# Mainboard_RMII_Interface.net
KiCad netlist of a schematic drawn in Altium Designer
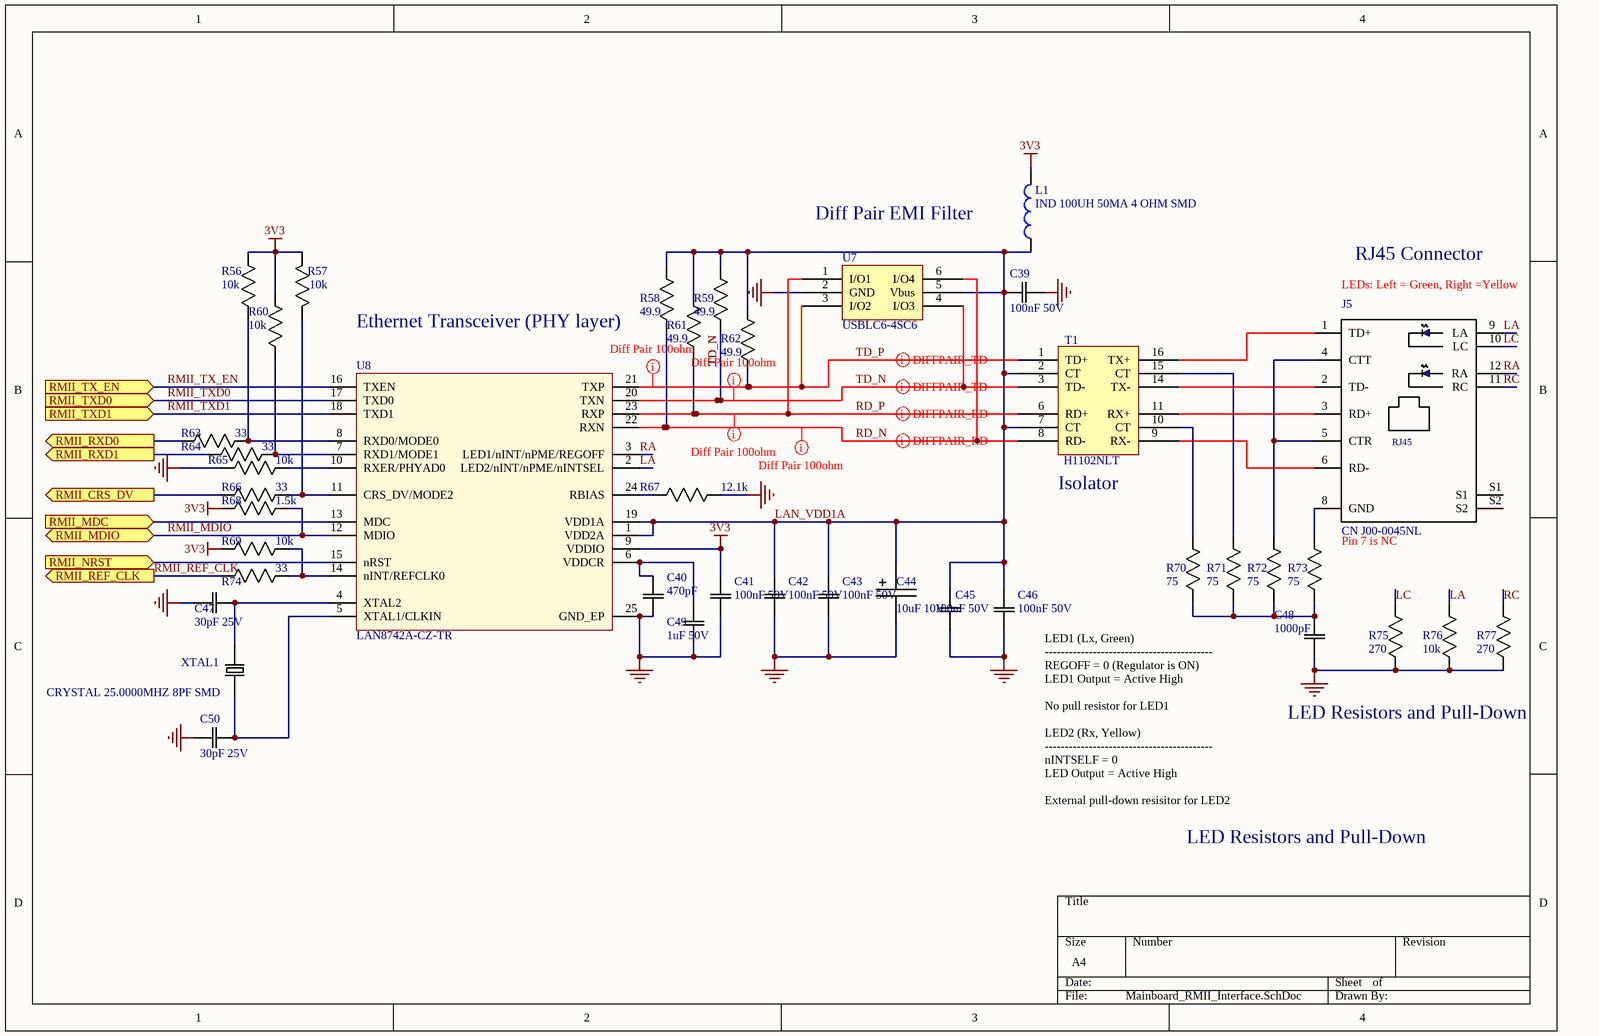
[diagram p0: Mainboard_RMII_Interface.SchDoc]

(export (version "E")
  (design (tool "Eeschema 10.0.6"))
  (components
    (comp (ref "C39")
      (value "100nF 50V")
      (footprint "0805")
      (description "CAP CER 0.1UF 50V X7R 0805")
      (fields (field (name "TOLERANCE") "10%"))
      (libsource (lib "") (part "CAP 100nF 50V_1"))
    )
    (comp (ref "C40")
      (value "470pF")
      (footprint "0805")
      (description "CAP CER 470PF 50V X7R 0603/0805")
      (fields (field (name "TOLERANCE") "10%"))
      (libsource (lib "AltiumLibraries") (part "CAP 470pF 50V"))
    )
    (comp (ref "C41")
      (value "100nF 50V")
      (footprint "0805")
      (description "CAP CER 0.1UF 50V X7R 0805")
      (fields (field (name "TOLERANCE") "10%"))
      (libsource (lib "AltiumLibraries") (part "CAP 100nF 50V"))
    )
    (comp (ref "C42")
      (value "100nF 50V")
      (footprint "0805")
      (description "CAP CER 0.1UF 50V X7R 0805")
      (fields (field (name "TOLERANCE") "10%"))
      (libsource (lib "AltiumLibraries") (part "CAP 100nF 50V"))
    )
    (comp (ref "C43")
      (value "100nF 50V")
      (footprint "0805")
      (description "CAP CER 0.1UF 50V X7R 0805")
      (fields (field (name "TOLERANCE") "10%"))
      (libsource (lib "AltiumLibraries") (part "CAP 100nF 50V"))
    )
    (comp (ref "C44")
      (value "10uF 10V")
      (footprint "1206 Polarized")
      (description "CAP TANT 10UF 10V 1206")
      (fields (field (name "TOLERANCE") "10%"))
      (libsource (lib "AltiumLibraries") (part "CAP TANT 10uF 10V"))
    )
    (comp (ref "C45")
      (value "100nF 50V")
      (footprint "0805")
      (description "CAP CER 0.1UF 50V X7R 0805")
      (fields (field (name "TOLERANCE") "10%"))
      (libsource (lib "AltiumLibraries") (part "CAP 100nF 50V"))
    )
    (comp (ref "C46")
      (value "100nF 50V")
      (footprint "0805")
      (description "CAP CER 0.1UF 50V X7R 0805")
      (fields (field (name "TOLERANCE") "10%"))
      (libsource (lib "AltiumLibraries") (part "CAP 100nF 50V"))
    )
    (comp (ref "C47")
      (value "30pF 25V")
      (footprint "0805")
      (description "CAP CER 30PF 25V NP0 0805")
      (fields (field (name "TOLERANCE") "20%"))
      (libsource (lib "AltiumLibraries") (part "CAP 30pF 25V"))
    )
    (comp (ref "C48")
      (value "1000pF")
      (footprint "0603")
      (description "CAP CER 1000PF 50V X7R 0603/0805")
      (fields (field (name "TOLERANCE") "10%"))
      (libsource (lib "AltiumLibraries") (part "CAP 1000pF 50V"))
    )
    (comp (ref "C49")
      (value "1uF 50V")
      (footprint "0805")
      (description "CAP CER 1UF 50V X7R 0805")
      (fields (field (name "TOLERANCE") "10%"))
      (libsource (lib "AltiumLibraries") (part "CAP 1uF 50V"))
    )
    (comp (ref "C50")
      (value "30pF 25V")
      (footprint "0805")
      (description "CAP CER 30PF 25V NP0 0805")
      (fields (field (name "TOLERANCE") "20%"))
      (libsource (lib "AltiumLibraries") (part "CAP 30pF 25V"))
    )
    (comp (ref "J5")
      (value "CN J00-0045NL")
      (footprint "RJ45 J00-0045NL")
      (description "CN MAGJACK 1PORT 100 BASE-TX")
      (fields (field (name "MF") "Pulse Electronics") (field (name "MP") "J00-0045NL"))
      (libsource (lib "AltiumLibraries") (part "CN MAGJACK"))
    )
    (comp (ref "L1")
      (value "IND 100UH 50MA 4 OHM SMD")
      (footprint "0805")
      (description "100µH Unshielded Wirewound Inductor 50mA 4Ohm 0805 (2012 Metric)")
      (fields (field (name "MF") "Taiyo Yuden") (field (name "MP") "LBR2012T101K"))
      (libsource (lib "AltiumLibraries") (part "IND 100UH 50MA 4 OHM SMD"))
    )
    (comp (ref "R56")
      (value "10k")
      (footprint "0805")
      (description "RES SMD 10K OHM 1% 1/8W 0805")
      (fields (field (name "TOLERANCE") "1%"))
      (libsource (lib "") (part "RES 10k 1/8W - 1%_1"))
    )
    (comp (ref "R57")
      (value "10k")
      (footprint "0805")
      (description "RES SMD 10K OHM 1% 1/8W 0805")
      (fields (field (name "TOLERANCE") "1%"))
      (libsource (lib "") (part "RES 10k 1/8W - 1%_1"))
    )
    (comp (ref "R58")
      (value "49.9")
      (footprint "0805")
      (description "RES SMD 49.9 OHM 1% 1/8W 0805")
      (fields (field (name "TOLERANCE") "1%"))
      (libsource (lib "AltiumLibraries") (part "RES 49.9 1/8W"))
    )
    (comp (ref "R59")
      (value "49.9")
      (footprint "0805")
      (description "RES SMD 49.9 OHM 1% 1/8W 0805")
      (fields (field (name "TOLERANCE") "1%"))
      (libsource (lib "AltiumLibraries") (part "RES 49.9 1/8W"))
    )
    (comp (ref "R60")
      (value "10k")
      (footprint "0805")
      (description "RES SMD 10K OHM 1% 1/8W 0805")
      (fields (field (name "TOLERANCE") "1%"))
      (libsource (lib "") (part "RES 10k 1/8W - 1%_1"))
    )
    (comp (ref "R61")
      (value "49.9")
      (footprint "0805")
      (description "RES SMD 49.9 OHM 1% 1/8W 0805")
      (fields (field (name "TOLERANCE") "1%"))
      (libsource (lib "AltiumLibraries") (part "RES 49.9 1/8W"))
    )
    (comp (ref "R62")
      (value "49.9")
      (footprint "0805")
      (description "RES SMD 49.9 OHM 1% 1/8W 0805")
      (fields (field (name "TOLERANCE") "1%"))
      (libsource (lib "AltiumLibraries") (part "RES 49.9 1/8W"))
    )
    (comp (ref "R63")
      (value "33")
      (footprint "0805")
      (description "RES SMD 33 OHM 1% 1/8W 0805")
      (fields (field (name "TOLERANCE") "1%"))
      (libsource (lib "AltiumLibraries") (part "RES 33.0 1/8W - 1%"))
    )
    (comp (ref "R64")
      (value "33")
      (footprint "0805")
      (description "RES SMD 33 OHM 1% 1/8W 0805")
      (fields (field (name "TOLERANCE") "1%"))
      (libsource (lib "AltiumLibraries") (part "RES 33.0 1/8W - 1%"))
    )
    (comp (ref "R65")
      (value "10k")
      (footprint "0805")
      (description "RES SMD 10K OHM 1% 1/8W 0805")
      (fields (field (name "TOLERANCE") "1%"))
      (libsource (lib "AltiumLibraries") (part "RES 10k 1/8W - 1%"))
    )
    (comp (ref "R66")
      (value "33")
      (footprint "0805")
      (description "RES SMD 33 OHM 1% 1/8W 0805")
      (fields (field (name "TOLERANCE") "1%"))
      (libsource (lib "AltiumLibraries") (part "RES 33.0 1/8W - 1%"))
    )
    (comp (ref "R67")
      (value "12.1k")
      (footprint "0805")
      (description "RES SMD 12.1K OHM 1% 1/8W 0805")
      (fields (field (name "TOLERANCE") "1%"))
      (libsource (lib "AltiumLibraries") (part "RES 12.1k 1/8W"))
    )
    (comp (ref "R68")
      (value "1.5k")
      (footprint "0805")
      (description "RES SMD 1.5K OHM 1% 1/8W 0805")
      (fields (field (name "TOLERANCE") "1%"))
      (libsource (lib "AltiumLibraries") (part "RES 1.5k 1/8W - 1%"))
    )
    (comp (ref "R69")
      (value "10k")
      (footprint "0805")
      (description "RES SMD 10K OHM 1% 1/8W 0805")
      (fields (field (name "TOLERANCE") "1%"))
      (libsource (lib "AltiumLibraries") (part "RES 10k 1/8W - 1%"))
    )
    (comp (ref "R70")
      (value "75")
      (footprint "0805")
      (description "RES SMD 75 OHM 1% 1/8W 0805")
      (fields (field (name "TOLERANCE") "1%"))
      (libsource (lib "AltiumLibraries") (part "RES 75.0 1/8W - 1%"))
    )
    (comp (ref "R71")
      (value "75")
      (footprint "0805")
      (description "RES SMD 75 OHM 1% 1/8W 0805")
      (fields (field (name "TOLERANCE") "1%"))
      (libsource (lib "AltiumLibraries") (part "RES 75.0 1/8W - 1%"))
    )
    (comp (ref "R72")
      (value "75")
      (footprint "0805")
      (description "RES SMD 75 OHM 1% 1/8W 0805")
      (fields (field (name "TOLERANCE") "1%"))
      (libsource (lib "AltiumLibraries") (part "RES 75.0 1/8W - 1%"))
    )
    (comp (ref "R73")
      (value "75")
      (footprint "0805")
      (description "RES SMD 75 OHM 1% 1/8W 0805")
      (fields (field (name "TOLERANCE") "1%"))
      (libsource (lib "AltiumLibraries") (part "RES 75.0 1/8W - 1%"))
    )
    (comp (ref "R74")
      (value "33")
      (footprint "0805")
      (description "RES SMD 33 OHM 1% 1/8W 0805")
      (fields (field (name "TOLERANCE") "1%"))
      (libsource (lib "AltiumLibraries") (part "RES 33.0 1/8W - 1%"))
    )
    (comp (ref "R75")
      (value "270")
      (footprint "0805")
      (description "RES SMD 270 OHM 5% 1/8W 0805")
      (fields (field (name "TOLERANCE") "5%"))
      (libsource (lib "AltiumLibraries") (part "RES 270.0 1/8W"))
    )
    (comp (ref "R76")
      (value "10k")
      (footprint "0805")
      (description "RES SMD 10K OHM 1% 1/8W 0805")
      (fields (field (name "TOLERANCE") "1%"))
      (libsource (lib "") (part "RES 10k 1/8W - 1%_1"))
    )
    (comp (ref "R77")
      (value "270")
      (footprint "0805")
      (description "RES SMD 270 OHM 5% 1/8W 0805")
      (fields (field (name "TOLERANCE") "5%"))
      (libsource (lib "AltiumLibraries") (part "RES 270.0 1/8W"))
    )
    (comp (ref "T1")
      (value "H1102NLT")
      (footprint "TRANSFORMER")
      (fields (field (name "MF") "Pulse Electronics") (field (name "MP") "H1102NL"))
      (libsource (lib "AltiumLibraries") (part "XFRMR H1102NLT"))
    )
    (comp (ref "U7")
      (value "USBLC6-4SC6")
      (footprint "SOT23-6L")
      (libsource (lib "AltiumLibraries") (part "USBLC6-4SC6"))
    )
    (comp (ref "U8")
      (value "LAN8742A-CZ-TR")
      (footprint "24-QFN (4x4)")
      (fields (field (name "MF") "Microchip Technology"))
      (libsource (lib "AltiumLibraries") (part "LAN8742A-CZ-TR"))
    )
    (comp (ref "XTAL1")
      (value "CRYSTAL 25.0000MHZ 8PF SMD")
      (footprint "SMD-2")
      (description "25MHz ±50ppm Crystal 8pF 70 Ohms 2-SMD, No Lead")
      (fields (field (name "MP") "NX5032GA-25.000000MHZ-LN-CD-1") (field (name "MF") "NDK America, Inc."))
      (libsource (lib "AltiumLibraries") (part "XTAL 25MHZ 8PF SMD"))
    )
  )
  (nets
    (net (code "1") (name "/LA") (class "Default")
      (node (ref "J5") (pin "9") (pinfunction "LA_9") (pintype "passive"))
      (node (ref "R76") (pin "1") (pinfunction "R1_1") (pintype "passive"))
      (node (ref "U8") (pin "2") (pinfunction "LED2/nINT/nPME/nINTSEL_2") (pintype "passive"))
    )
    (net (code "2") (name "/LAN_VDD1A") (class "Default")
      (node (ref "C39") (pin "1") (pinfunction "C1_1") (pintype "passive"))
      (node (ref "C42") (pin "2") (pinfunction "C2_2") (pintype "passive"))
      (node (ref "C43") (pin "2") (pinfunction "C2_2") (pintype "passive"))
      (node (ref "C44") (pin "1") (pinfunction "P$1_1") (pintype "passive"))
      (node (ref "C45") (pin "2") (pinfunction "C2_2") (pintype "passive"))
      (node (ref "C46") (pin "2") (pinfunction "C2_2") (pintype "passive"))
      (node (ref "L1") (pin "1") (pinfunction "1_1") (pintype "passive"))
      (node (ref "R58") (pin "1") (pinfunction "R1_1") (pintype "passive"))
      (node (ref "R59") (pin "1") (pinfunction "R1_1") (pintype "passive"))
      (node (ref "R61") (pin "1") (pinfunction "R1_1") (pintype "passive"))
      (node (ref "R62") (pin "1") (pinfunction "R1_1") (pintype "passive"))
      (node (ref "T1") (pin "2") (pinfunction "CT_2") (pintype "passive"))
      (node (ref "T1") (pin "7") (pinfunction "CT_7") (pintype "passive"))
      (node (ref "U7") (pin "5") (pinfunction "Vbus_5") (pintype "passive"))
      (node (ref "U8") (pin "1") (pinfunction "VDD2A_1") (pintype "passive"))
      (node (ref "U8") (pin "19") (pinfunction "VDD1A_19") (pintype "passive"))
    )
    (net (code "3") (name "/LC") (class "Default")
      (node (ref "J5") (pin "10") (pinfunction "LC_10") (pintype "passive"))
      (node (ref "R75") (pin "1") (pinfunction "R1_1") (pintype "passive"))
    )
    (net (code "4") (name "/RA") (class "Default")
      (node (ref "J5") (pin "12") (pinfunction "RA_12") (pintype "passive"))
      (node (ref "U8") (pin "3") (pinfunction "LED1/nINT/nPME/REGOFF_3") (pintype "passive"))
    )
    (net (code "5") (name "/RC") (class "Default")
      (node (ref "J5") (pin "11") (pinfunction "RC_11") (pintype "passive"))
      (node (ref "R77") (pin "1") (pinfunction "R1_1") (pintype "passive"))
    )
    (net (code "6") (name "/RD_N") (class "Default")
      (node (ref "R58") (pin "2") (pinfunction "R2_2") (pintype "passive"))
      (node (ref "T1") (pin "8") (pinfunction "RD-_8") (pintype "passive"))
      (node (ref "U7") (pin "6") (pinfunction "I/O4_6") (pintype "passive"))
      (node (ref "U8") (pin "22") (pinfunction "RXN_22") (pintype "passive"))
    )
    (net (code "7") (name "/RD_P") (class "Default")
      (node (ref "R61") (pin "2") (pinfunction "R2_2") (pintype "passive"))
      (node (ref "T1") (pin "6") (pinfunction "RD+_6") (pintype "passive"))
      (node (ref "U7") (pin "1") (pinfunction "I/O1_1") (pintype "passive"))
      (node (ref "U8") (pin "23") (pinfunction "RXP_23") (pintype "passive"))
    )
    (net (code "8") (name "/RMII_CRS_DV") (class "Default")
      (node (ref "R66") (pin "2") (pinfunction "R2_2") (pintype "passive"))
    )
    (net (code "9") (name "/RMII_MDC") (class "Default")
      (node (ref "U8") (pin "13") (pinfunction "MDC_13") (pintype "passive"))
    )
    (net (code "10") (name "/RMII_MDIO") (class "Default")
      (node (ref "R68") (pin "1") (pinfunction "R1_1") (pintype "passive"))
      (node (ref "U8") (pin "12") (pinfunction "MDIO_12") (pintype "passive"))
    )
    (net (code "11") (name "/RMII_NRST") (class "Default")
      (node (ref "U8") (pin "15") (pinfunction "nRST_15") (pintype "passive"))
    )
    (net (code "12") (name "/RMII_REF_CLK") (class "Default")
      (node (ref "R74") (pin "2") (pinfunction "R2_2") (pintype "passive"))
    )
    (net (code "13") (name "/RMII_RXD0") (class "Default")
      (node (ref "R63") (pin "2") (pinfunction "R2_2") (pintype "passive"))
    )
    (net (code "14") (name "/RMII_RXD1") (class "Default")
      (node (ref "R64") (pin "2") (pinfunction "R2_2") (pintype "passive"))
    )
    (net (code "15") (name "/RMII_TXD0") (class "Default")
      (node (ref "U8") (pin "17") (pinfunction "TXD0_17") (pintype "passive"))
    )
    (net (code "16") (name "/RMII_TXD1") (class "Default")
      (node (ref "U8") (pin "18") (pinfunction "TXD1_18") (pintype "passive"))
    )
    (net (code "17") (name "/RMII_TX_EN") (class "Default")
      (node (ref "U8") (pin "16") (pinfunction "TXEN_16") (pintype "passive"))
    )
    (net (code "18") (name "/TD_N") (class "Default")
      (node (ref "R59") (pin "2") (pinfunction "R2_2") (pintype "passive"))
      (node (ref "T1") (pin "3") (pinfunction "TD-_3") (pintype "passive"))
      (node (ref "U7") (pin "4") (pinfunction "I/O3_4") (pintype "passive"))
      (node (ref "U8") (pin "20") (pinfunction "TXN_20") (pintype "passive"))
    )
    (net (code "19") (name "/TD_P") (class "Default")
      (node (ref "R62") (pin "2") (pinfunction "R2_2") (pintype "passive"))
      (node (ref "T1") (pin "1") (pinfunction "TD+_1") (pintype "passive"))
      (node (ref "U7") (pin "3") (pinfunction "I/O2_3") (pintype "passive"))
      (node (ref "U8") (pin "21") (pinfunction "TXP_21") (pintype "passive"))
    )
    (net (code "20") (name "3V3") (class "Default")
      (node (ref "C41") (pin "2") (pinfunction "C2_2") (pintype "passive"))
      (node (ref "L1") (pin "2") (pinfunction "2_2") (pintype "passive"))
      (node (ref "R56") (pin "1") (pinfunction "R1_1") (pintype "passive"))
      (node (ref "R57") (pin "1") (pinfunction "R1_1") (pintype "passive"))
      (node (ref "R60") (pin "1") (pinfunction "R1_1") (pintype "passive"))
      (node (ref "R68") (pin "2") (pinfunction "R2_2") (pintype "passive"))
      (node (ref "R69") (pin "2") (pinfunction "R2_2") (pintype "passive"))
      (node (ref "U8") (pin "9") (pinfunction "VDDIO_9") (pintype "passive"))
    )
    (net (code "21") (name "GND") (class "Default")
      (node (ref "C39") (pin "2") (pinfunction "C2_2") (pintype "passive"))
      (node (ref "C40") (pin "1") (pinfunction "C1_1") (pintype "passive"))
      (node (ref "C41") (pin "1") (pinfunction "C1_1") (pintype "passive"))
      (node (ref "C42") (pin "1") (pinfunction "C1_1") (pintype "passive"))
      (node (ref "C43") (pin "1") (pinfunction "C1_1") (pintype "passive"))
      (node (ref "C44") (pin "2") (pinfunction "P$2_2") (pintype "passive"))
      (node (ref "C45") (pin "1") (pinfunction "C1_1") (pintype "passive"))
      (node (ref "C46") (pin "1") (pinfunction "C1_1") (pintype "passive"))
      (node (ref "C47") (pin "1") (pinfunction "C1_1") (pintype "passive"))
      (node (ref "C48") (pin "1") (pinfunction "C1_1") (pintype "passive"))
      (node (ref "C49") (pin "1") (pinfunction "C1_1") (pintype "passive"))
      (node (ref "C50") (pin "1") (pinfunction "C1_1") (pintype "passive"))
      (node (ref "R65") (pin "2") (pinfunction "R2_2") (pintype "passive"))
      (node (ref "R67") (pin "1") (pinfunction "R1_1") (pintype "passive"))
      (node (ref "R75") (pin "2") (pinfunction "R2_2") (pintype "passive"))
      (node (ref "R76") (pin "2") (pinfunction "R2_2") (pintype "passive"))
      (node (ref "R77") (pin "2") (pinfunction "R2_2") (pintype "passive"))
      (node (ref "U7") (pin "2") (pinfunction "GND_2") (pintype "passive"))
      (node (ref "U8") (pin "25") (pinfunction "GND_EP_25") (pintype "passive"))
    )
    (net (code "22") (name "Net-(C40-C2)") (class "Default")
      (node (ref "C40") (pin "2") (pinfunction "C2_2") (pintype "passive"))
      (node (ref "C49") (pin "2") (pinfunction "C2_2") (pintype "passive"))
      (node (ref "U8") (pin "6") (pinfunction "VDDCR_6") (pintype "passive"))
    )
    (net (code "23") (name "Net-(C47-C2)") (class "Default")
      (node (ref "C47") (pin "2") (pinfunction "C2_2") (pintype "passive"))
      (node (ref "U8") (pin "4") (pinfunction "XTAL2_4") (pintype "passive"))
      (node (ref "XTAL1") (pin "2") (pinfunction "2_2") (pintype "passive"))
    )
    (net (code "24") (name "Net-(C48-C2)") (class "Default")
      (node (ref "C48") (pin "2") (pinfunction "C2_2") (pintype "passive"))
      (node (ref "R70") (pin "2") (pinfunction "R2_2") (pintype "passive"))
      (node (ref "R71") (pin "2") (pinfunction "R2_2") (pintype "passive"))
      (node (ref "R72") (pin "2") (pinfunction "R2_2") (pintype "passive"))
      (node (ref "R73") (pin "2") (pinfunction "R2_2") (pintype "passive"))
    )
    (net (code "25") (name "Net-(C50-C2)") (class "Default")
      (node (ref "C50") (pin "2") (pinfunction "C2_2") (pintype "passive"))
      (node (ref "U8") (pin "5") (pinfunction "XTAL1/CLKIN_5") (pintype "passive"))
      (node (ref "XTAL1") (pin "1") (pinfunction "1_1") (pintype "passive"))
    )
    (net (code "26") (name "Net-(J5-CTR)") (class "Default")
      (node (ref "J5") (pin "4") (pinfunction "CTT_4") (pintype "passive"))
      (node (ref "J5") (pin "5") (pinfunction "CTR_5") (pintype "passive"))
      (node (ref "R72") (pin "1") (pinfunction "R1_1") (pintype "passive"))
    )
    (net (code "27") (name "Net-(J5-GND)") (class "Default")
      (node (ref "J5") (pin "8") (pinfunction "GND_8") (pintype "passive"))
      (node (ref "R73") (pin "1") (pinfunction "R1_1") (pintype "passive"))
    )
    (net (code "28") (name "Net-(J5-RD+)") (class "Default")
      (node (ref "J5") (pin "3") (pinfunction "RD+_3") (pintype "passive"))
      (node (ref "T1") (pin "11") (pinfunction "RX+_11") (pintype "passive"))
    )
    (net (code "29") (name "Net-(J5-RD-)") (class "Default")
      (node (ref "J5") (pin "6") (pinfunction "RD-_6") (pintype "passive"))
      (node (ref "T1") (pin "9") (pinfunction "RX-_9") (pintype "passive"))
    )
    (net (code "30") (name "Net-(J5-TD+)") (class "Default")
      (node (ref "J5") (pin "1") (pinfunction "TD+_1") (pintype "passive"))
      (node (ref "T1") (pin "16") (pinfunction "TX+_16") (pintype "passive"))
    )
    (net (code "31") (name "Net-(J5-TD-)") (class "Default")
      (node (ref "J5") (pin "2") (pinfunction "TD-_2") (pintype "passive"))
      (node (ref "T1") (pin "14") (pinfunction "TX-_14") (pintype "passive"))
    )
    (net (code "32") (name "Net-(R56-R2)") (class "Default")
      (node (ref "R56") (pin "2") (pinfunction "R2_2") (pintype "passive"))
      (node (ref "R63") (pin "1") (pinfunction "R1_1") (pintype "passive"))
      (node (ref "U8") (pin "8") (pinfunction "RXD0/MODE0_8") (pintype "passive"))
    )
    (net (code "33") (name "Net-(R57-R2)") (class "Default")
      (node (ref "R57") (pin "2") (pinfunction "R2_2") (pintype "passive"))
      (node (ref "R66") (pin "1") (pinfunction "R1_1") (pintype "passive"))
      (node (ref "U8") (pin "11") (pinfunction "CRS_DV/MODE2_11") (pintype "passive"))
    )
    (net (code "34") (name "Net-(R60-R2)") (class "Default")
      (node (ref "R60") (pin "2") (pinfunction "R2_2") (pintype "passive"))
      (node (ref "R64") (pin "1") (pinfunction "R1_1") (pintype "passive"))
      (node (ref "U8") (pin "7") (pinfunction "RXD1/MODE1_7") (pintype "passive"))
    )
    (net (code "35") (name "Net-(R65-R1)") (class "Default")
      (node (ref "R65") (pin "1") (pinfunction "R1_1") (pintype "passive"))
      (node (ref "U8") (pin "10") (pinfunction "RXER/PHYAD0_10") (pintype "passive"))
    )
    (net (code "36") (name "Net-(R67-R2)") (class "Default")
      (node (ref "R67") (pin "2") (pinfunction "R2_2") (pintype "passive"))
      (node (ref "U8") (pin "24") (pinfunction "RBIAS_24") (pintype "passive"))
    )
    (net (code "37") (name "Net-(R69-R1)") (class "Default")
      (node (ref "R69") (pin "1") (pinfunction "R1_1") (pintype "passive"))
      (node (ref "R74") (pin "1") (pinfunction "R1_1") (pintype "passive"))
      (node (ref "U8") (pin "14") (pinfunction "nINT/REFCLK0_14") (pintype "passive"))
    )
    (net (code "38") (name "Net-(R70-R1)") (class "Default")
      (node (ref "R70") (pin "1") (pinfunction "R1_1") (pintype "passive"))
      (node (ref "T1") (pin "10") (pinfunction "CT_10") (pintype "passive"))
    )
    (net (code "39") (name "Net-(R71-R1)") (class "Default")
      (node (ref "R71") (pin "1") (pinfunction "R1_1") (pintype "passive"))
      (node (ref "T1") (pin "15") (pinfunction "CT_15") (pintype "passive"))
    )
    (net (code "40") (name "unconnected-(J5-PadS1)") (class "Default")
      (node (ref "J5") (pin "S1") (pinfunction "S1_S1") (pintype "passive"))
    )
    (net (code "41") (name "unconnected-(J5-PadS2)") (class "Default")
      (node (ref "J5") (pin "S2") (pinfunction "S2_S2") (pintype "passive"))
    )
  )
)
